# untitled.net
KiCad netlist of a schematic drawn in EAGLE
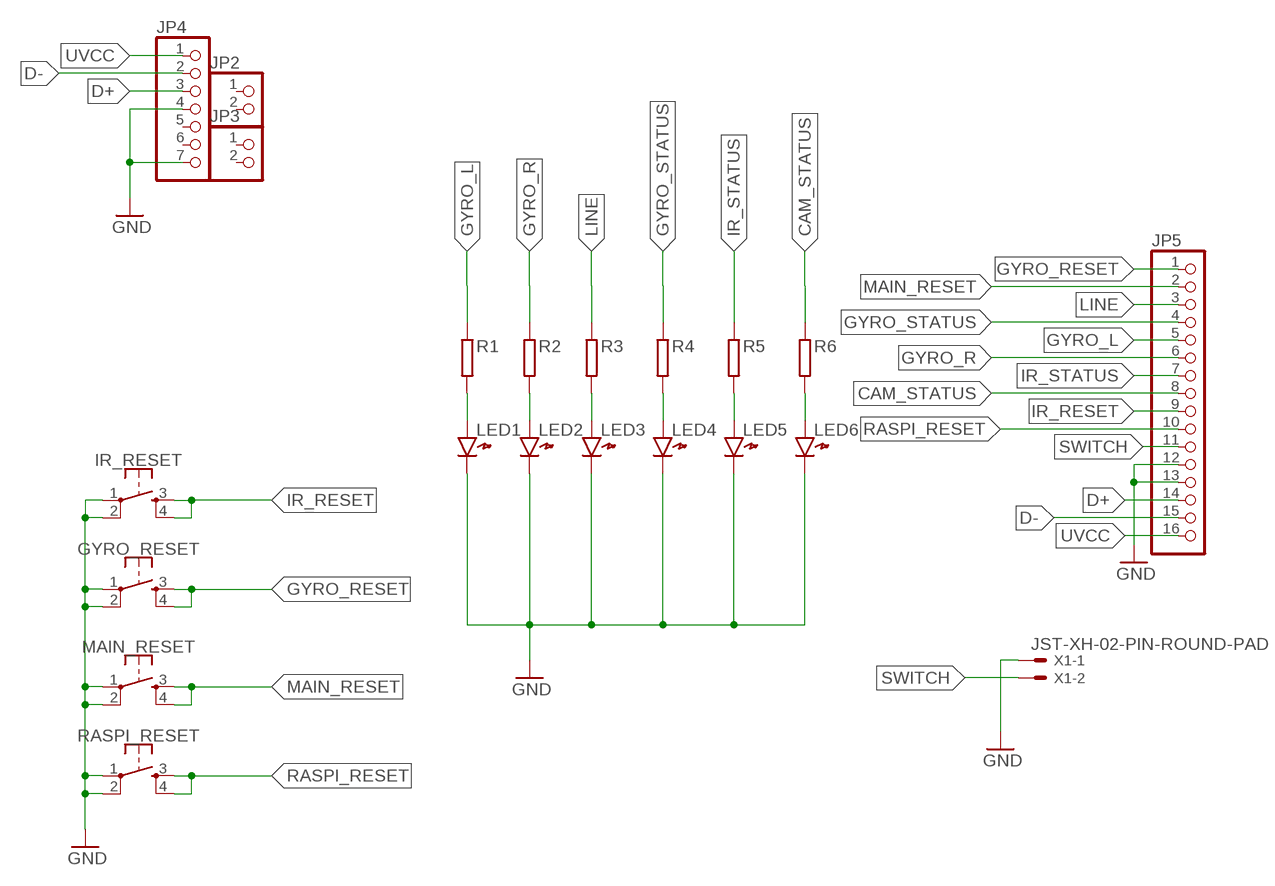
[diagram p0: schematic, sheet 1]

(export (version "E")
  (design (tool "Eeschema 10.0.6"))
  (components
    (comp (ref "GYRO_RESET")
      (value "MOMENTARY-SWITCH-SPST-2-SMD-5.2MM")
      (footprint "eagle-import:TACTILE_SWITCH_SMD_5.2MM")
      (libsource (lib "eagle-import") (part "MOMENTARY-SWITCH-SPST-2-SMD-5.2MM"))
    )
    (comp (ref "IR_RESET")
      (value "MOMENTARY-SWITCH-SPST-2-SMD-5.2MM")
      (footprint "eagle-import:TACTILE_SWITCH_SMD_5.2MM")
      (libsource (lib "eagle-import") (part "MOMENTARY-SWITCH-SPST-2-SMD-5.2MM"))
    )
    (comp (ref "JP2")
      (value "PINHD-1X2")
      (footprint "eagle-import:1X02")
      (libsource (lib "eagle-import") (part "PINHD-1X2"))
    )
    (comp (ref "JP3")
      (value "PINHD-1X2")
      (footprint "eagle-import:1X02")
      (libsource (lib "eagle-import") (part "PINHD-1X2"))
    )
    (comp (ref "JP4")
      (value "PINHD-1X7")
      (footprint "eagle-import:1X07")
      (libsource (lib "eagle-import") (part "PINHD-1X7"))
    )
    (comp (ref "JP5")
      (value "PINHD-1X16")
      (footprint "eagle-import:1X16")
      (libsource (lib "eagle-import") (part "PINHD-1X16"))
    )
    (comp (ref "LED1")
      (value "LED1608")
      (footprint "eagle-import:LED1608")
      (libsource (lib "eagle-import") (part "LED1608"))
    )
    (comp (ref "LED2")
      (value "LED1608")
      (footprint "eagle-import:LED1608")
      (libsource (lib "eagle-import") (part "LED1608"))
    )
    (comp (ref "LED3")
      (value "LED1608")
      (footprint "eagle-import:LED1608")
      (libsource (lib "eagle-import") (part "LED1608"))
    )
    (comp (ref "LED4")
      (value "LED1608")
      (footprint "eagle-import:LED1608")
      (libsource (lib "eagle-import") (part "LED1608"))
    )
    (comp (ref "LED5")
      (value "LED1608")
      (footprint "eagle-import:LED1608")
      (libsource (lib "eagle-import") (part "LED1608"))
    )
    (comp (ref "LED6")
      (value "LED1608")
      (footprint "eagle-import:LED1608")
      (libsource (lib "eagle-import") (part "LED1608"))
    )
    (comp (ref "MAIN_RESET")
      (value "MOMENTARY-SWITCH-SPST-2-SMD-5.2MM")
      (footprint "eagle-import:TACTILE_SWITCH_SMD_5.2MM")
      (libsource (lib "eagle-import") (part "MOMENTARY-SWITCH-SPST-2-SMD-5.2MM"))
    )
    (comp (ref "R1")
      (value "RESISTOR1608")
      (footprint "eagle-import:SMD1608")
      (libsource (lib "eagle-import") (part "RESISTOR1608"))
    )
    (comp (ref "R2")
      (value "RESISTOR1608")
      (footprint "eagle-import:SMD1608")
      (libsource (lib "eagle-import") (part "RESISTOR1608"))
    )
    (comp (ref "R3")
      (value "RESISTOR1608")
      (footprint "eagle-import:SMD1608")
      (libsource (lib "eagle-import") (part "RESISTOR1608"))
    )
    (comp (ref "R4")
      (value "RESISTOR1608")
      (footprint "eagle-import:SMD1608")
      (libsource (lib "eagle-import") (part "RESISTOR1608"))
    )
    (comp (ref "R5")
      (value "RESISTOR1608")
      (footprint "eagle-import:SMD1608")
      (libsource (lib "eagle-import") (part "RESISTOR1608"))
    )
    (comp (ref "R6")
      (value "RESISTOR1608")
      (footprint "eagle-import:SMD1608")
      (libsource (lib "eagle-import") (part "RESISTOR1608"))
    )
    (comp (ref "RASPI_RESET")
      (value "MOMENTARY-SWITCH-SPST-2-SMD-5.2MM")
      (footprint "eagle-import:TACTILE_SWITCH_SMD_5.2MM")
      (libsource (lib "eagle-import") (part "MOMENTARY-SWITCH-SPST-2-SMD-5.2MM"))
    )
    (comp (ref "X1")
      (value "JST-XH-02-PIN-ROUND-PAD")
      (footprint "eagle-import:JST-XH-02-PACKAGE-ROUND-PAD")
      (libsource (lib "eagle-import") (part "JST-XH-02-PIN-ROUND-PAD"))
    )
  )
  (nets
    (net (code "1") (name "CAM_STATUS") (class "Default")
      (node (ref "JP5") (pin "8") (pinfunction "8_8") (pintype "passive"))
      (node (ref "R6") (pin "1") (pinfunction "1_1") (pintype "passive"))
    )
    (net (code "2") (name "D+") (class "Default")
      (node (ref "JP4") (pin "3") (pinfunction "3_3") (pintype "passive"))
      (node (ref "JP5") (pin "14") (pinfunction "14_14") (pintype "passive"))
    )
    (net (code "3") (name "D-") (class "Default")
      (node (ref "JP4") (pin "2") (pinfunction "2_2") (pintype "passive"))
      (node (ref "JP5") (pin "15") (pinfunction "15_15") (pintype "passive"))
    )
    (net (code "4") (name "GND") (class "Default")
      (node (ref "GYRO_RESET") (pin "1") (pinfunction "1_1") (pintype "passive"))
      (node (ref "GYRO_RESET") (pin "2") (pinfunction "2_2") (pintype "passive"))
      (node (ref "IR_RESET") (pin "1") (pinfunction "1_1") (pintype "passive"))
      (node (ref "IR_RESET") (pin "2") (pinfunction "2_2") (pintype "passive"))
      (node (ref "JP4") (pin "4") (pinfunction "4_4") (pintype "passive"))
      (node (ref "JP4") (pin "7") (pinfunction "7_7") (pintype "passive"))
      (node (ref "JP5") (pin "12") (pinfunction "12_12") (pintype "passive"))
      (node (ref "JP5") (pin "13") (pinfunction "13_13") (pintype "passive"))
      (node (ref "LED1") (pin "K") (pinfunction "K_K") (pintype "passive"))
      (node (ref "LED2") (pin "K") (pinfunction "K_K") (pintype "passive"))
      (node (ref "LED3") (pin "K") (pinfunction "K_K") (pintype "passive"))
      (node (ref "LED4") (pin "K") (pinfunction "K_K") (pintype "passive"))
      (node (ref "LED5") (pin "K") (pinfunction "K_K") (pintype "passive"))
      (node (ref "LED6") (pin "K") (pinfunction "K_K") (pintype "passive"))
      (node (ref "MAIN_RESET") (pin "1") (pinfunction "1_1") (pintype "passive"))
      (node (ref "MAIN_RESET") (pin "2") (pinfunction "2_2") (pintype "passive"))
      (node (ref "RASPI_RESET") (pin "1") (pinfunction "1_1") (pintype "passive"))
      (node (ref "RASPI_RESET") (pin "2") (pinfunction "2_2") (pintype "passive"))
      (node (ref "X1") (pin "1") (pinfunction "S_1") (pintype "passive"))
    )
    (net (code "5") (name "GYRO_L") (class "Default")
      (node (ref "JP5") (pin "5") (pinfunction "5_5") (pintype "passive"))
      (node (ref "R1") (pin "1") (pinfunction "1_1") (pintype "passive"))
    )
    (net (code "6") (name "GYRO_R") (class "Default")
      (node (ref "JP5") (pin "6") (pinfunction "6_6") (pintype "passive"))
      (node (ref "R2") (pin "1") (pinfunction "1_1") (pintype "passive"))
    )
    (net (code "7") (name "GYRO_RESET") (class "Default")
      (node (ref "GYRO_RESET") (pin "3") (pinfunction "3_3") (pintype "passive"))
      (node (ref "GYRO_RESET") (pin "4") (pinfunction "4_4") (pintype "passive"))
      (node (ref "JP5") (pin "1") (pinfunction "1_1") (pintype "passive"))
    )
    (net (code "8") (name "GYRO_STATUS") (class "Default")
      (node (ref "JP5") (pin "4") (pinfunction "4_4") (pintype "passive"))
      (node (ref "R4") (pin "1") (pinfunction "1_1") (pintype "passive"))
    )
    (net (code "9") (name "IR_RESET") (class "Default")
      (node (ref "IR_RESET") (pin "3") (pinfunction "3_3") (pintype "passive"))
      (node (ref "IR_RESET") (pin "4") (pinfunction "4_4") (pintype "passive"))
      (node (ref "JP5") (pin "9") (pinfunction "9_9") (pintype "passive"))
    )
    (net (code "10") (name "IR_STATUS") (class "Default")
      (node (ref "JP5") (pin "7") (pinfunction "7_7") (pintype "passive"))
      (node (ref "R5") (pin "1") (pinfunction "1_1") (pintype "passive"))
    )
    (net (code "11") (name "LINE") (class "Default")
      (node (ref "JP5") (pin "3") (pinfunction "3_3") (pintype "passive"))
      (node (ref "R3") (pin "1") (pinfunction "1_1") (pintype "passive"))
    )
    (net (code "12") (name "MAIN_RESET") (class "Default")
      (node (ref "JP5") (pin "2") (pinfunction "2_2") (pintype "passive"))
      (node (ref "MAIN_RESET") (pin "3") (pinfunction "3_3") (pintype "passive"))
      (node (ref "MAIN_RESET") (pin "4") (pinfunction "4_4") (pintype "passive"))
    )
    (net (code "13") (name "Net-(LED1-PadA)") (class "Default")
      (node (ref "LED1") (pin "A") (pinfunction "A_A") (pintype "passive"))
      (node (ref "R1") (pin "2") (pinfunction "2_2") (pintype "passive"))
    )
    (net (code "14") (name "Net-(LED2-PadA)") (class "Default")
      (node (ref "LED2") (pin "A") (pinfunction "A_A") (pintype "passive"))
      (node (ref "R2") (pin "2") (pinfunction "2_2") (pintype "passive"))
    )
    (net (code "15") (name "Net-(LED3-PadA)") (class "Default")
      (node (ref "LED3") (pin "A") (pinfunction "A_A") (pintype "passive"))
      (node (ref "R3") (pin "2") (pinfunction "2_2") (pintype "passive"))
    )
    (net (code "16") (name "Net-(LED4-PadA)") (class "Default")
      (node (ref "LED4") (pin "A") (pinfunction "A_A") (pintype "passive"))
      (node (ref "R4") (pin "2") (pinfunction "2_2") (pintype "passive"))
    )
    (net (code "17") (name "Net-(LED5-PadA)") (class "Default")
      (node (ref "LED5") (pin "A") (pinfunction "A_A") (pintype "passive"))
      (node (ref "R5") (pin "2") (pinfunction "2_2") (pintype "passive"))
    )
    (net (code "18") (name "Net-(LED6-PadA)") (class "Default")
      (node (ref "LED6") (pin "A") (pinfunction "A_A") (pintype "passive"))
      (node (ref "R6") (pin "2") (pinfunction "2_2") (pintype "passive"))
    )
    (net (code "19") (name "RASPI_RESET") (class "Default")
      (node (ref "JP5") (pin "10") (pinfunction "10_10") (pintype "passive"))
      (node (ref "RASPI_RESET") (pin "3") (pinfunction "3_3") (pintype "passive"))
      (node (ref "RASPI_RESET") (pin "4") (pinfunction "4_4") (pintype "passive"))
    )
    (net (code "20") (name "SWITCH") (class "Default")
      (node (ref "JP5") (pin "11") (pinfunction "11_11") (pintype "passive"))
      (node (ref "X1") (pin "2") (pinfunction "S_2") (pintype "passive"))
    )
    (net (code "21") (name "UVCC") (class "Default")
      (node (ref "JP4") (pin "1") (pinfunction "1_1") (pintype "passive"))
      (node (ref "JP5") (pin "16") (pinfunction "16_16") (pintype "passive"))
    )
    (net (code "22") (name "unconnected-(JP2-Pad1)") (class "Default")
      (node (ref "JP2") (pin "1") (pinfunction "1_1") (pintype "passive"))
    )
    (net (code "23") (name "unconnected-(JP2-Pad2)") (class "Default")
      (node (ref "JP2") (pin "2") (pinfunction "2_2") (pintype "passive"))
    )
    (net (code "24") (name "unconnected-(JP3-Pad1)") (class "Default")
      (node (ref "JP3") (pin "1") (pinfunction "1_1") (pintype "passive"))
    )
    (net (code "25") (name "unconnected-(JP3-Pad2)") (class "Default")
      (node (ref "JP3") (pin "2") (pinfunction "2_2") (pintype "passive"))
    )
    (net (code "26") (name "unconnected-(JP4-Pad5)") (class "Default")
      (node (ref "JP4") (pin "5") (pinfunction "5_5") (pintype "passive"))
    )
    (net (code "27") (name "unconnected-(JP4-Pad6)") (class "Default")
      (node (ref "JP4") (pin "6") (pinfunction "6_6") (pintype "passive"))
    )
  )
)
